# Vanocni.net
KiCad netlist of a schematic drawn in EAGLE
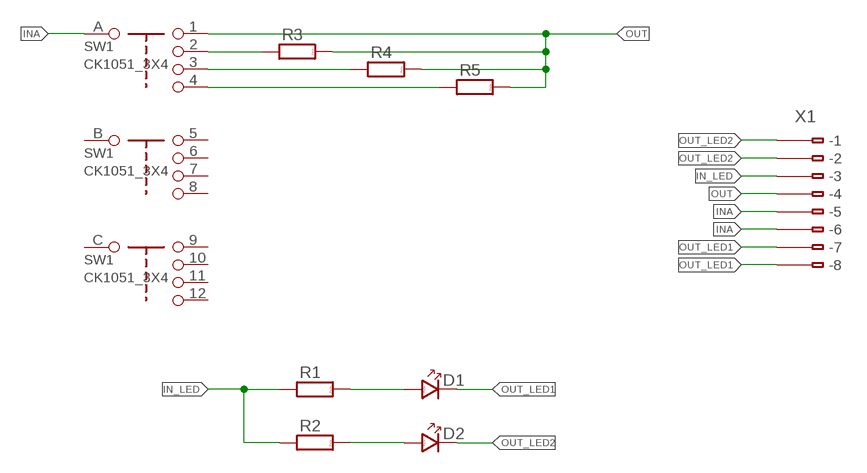
[diagram p0: schematic, sheet 1]

(export (version "E")
  (design (tool "Eeschema 10.0.6"))
  (components
    (comp (ref "D1")
      (value "LED_5")
      (footprint "eagle-import:LED_5")
      (libsource (lib "eagle-import") (part "LED_5"))
    )
    (comp (ref "D2")
      (value "LED_5")
      (footprint "eagle-import:LED_5")
      (libsource (lib "eagle-import") (part "LED_5"))
    )
    (comp (ref "R1")
      (value "R_7,5")
      (footprint "eagle-import:R-7,5")
      (libsource (lib "eagle-import") (part "R_7,5"))
    )
    (comp (ref "R2")
      (value "R_7,5")
      (footprint "eagle-import:R-7,5")
      (libsource (lib "eagle-import") (part "R_7,5"))
    )
    (comp (ref "R3")
      (value "R__2W")
      (footprint "eagle-import:R-_2W")
      (libsource (lib "eagle-import") (part "R__2W"))
    )
    (comp (ref "R4")
      (value "R__2W")
      (footprint "eagle-import:R-_2W")
      (libsource (lib "eagle-import") (part "R__2W"))
    )
    (comp (ref "R5")
      (value "R__2W")
      (footprint "eagle-import:R-_2W")
      (libsource (lib "eagle-import") (part "R__2W"))
    )
    (comp (ref "SW1")
      (value "CK1051_3X4")
      (footprint "eagle-import:SWITCH3X4")
      (libsource (lib "eagle-import") (part "CK1051_3X4"))
    )
    (comp (ref "X1")
      (value "233-508")
      (footprint "eagle-import:233-508")
      (fields (field (name "MF") "Wago Corporation") (field (name "MPN") "0233-0508"))
      (libsource (lib "eagle-import") (part "233-508"))
    )
  )
  (nets
    (net (code "1") (name "INA") (class "Default")
      (node (ref "SW1") (pin "A") (pinfunction "A_A") (pintype "passive"))
      (node (ref "X1") (pin "B5") (pinfunction "B-5_B5") (pintype "passive"))
      (node (ref "X1") (pin "B6") (pinfunction "B-6_B6") (pintype "passive"))
    )
    (net (code "2") (name "IN_LED") (class "Default")
      (node (ref "R1") (pin "1") (pinfunction "1_1") (pintype "passive"))
      (node (ref "R2") (pin "1") (pinfunction "1_1") (pintype "passive"))
      (node (ref "X1") (pin "B3") (pinfunction "B-3_B3") (pintype "passive"))
    )
    (net (code "3") (name "Net-(D1-PadA)") (class "Default")
      (node (ref "D1") (pin "A") (pinfunction "A_A") (pintype "passive"))
      (node (ref "R1") (pin "2") (pinfunction "2_2") (pintype "passive"))
    )
    (net (code "4") (name "Net-(D2-PadA)") (class "Default")
      (node (ref "D2") (pin "A") (pinfunction "A_A") (pintype "passive"))
      (node (ref "R2") (pin "2") (pinfunction "2_2") (pintype "passive"))
    )
    (net (code "5") (name "Net-(R3-Pad1)") (class "Default")
      (node (ref "R3") (pin "1") (pinfunction "1_1") (pintype "passive"))
      (node (ref "SW1") (pin "2") (pinfunction "2_2") (pintype "passive"))
    )
    (net (code "6") (name "Net-(R4-Pad1)") (class "Default")
      (node (ref "R4") (pin "1") (pinfunction "1_1") (pintype "passive"))
      (node (ref "SW1") (pin "3") (pinfunction "3_3") (pintype "passive"))
    )
    (net (code "7") (name "Net-(R5-Pad1)") (class "Default")
      (node (ref "R5") (pin "1") (pinfunction "1_1") (pintype "passive"))
      (node (ref "SW1") (pin "4") (pinfunction "4_4") (pintype "passive"))
    )
    (net (code "8") (name "OUT") (class "Default")
      (node (ref "R3") (pin "2") (pinfunction "2_2") (pintype "passive"))
      (node (ref "R4") (pin "2") (pinfunction "2_2") (pintype "passive"))
      (node (ref "R5") (pin "2") (pinfunction "2_2") (pintype "passive"))
      (node (ref "SW1") (pin "1") (pinfunction "1_1") (pintype "passive"))
      (node (ref "X1") (pin "B4") (pinfunction "B-4_B4") (pintype "passive"))
    )
    (net (code "9") (name "OUT_LED1") (class "Default")
      (node (ref "D1") (pin "K") (pinfunction "K_K") (pintype "passive"))
      (node (ref "X1") (pin "B7") (pinfunction "B-7_B7") (pintype "passive"))
      (node (ref "X1") (pin "B8") (pinfunction "B-8_B8") (pintype "passive"))
    )
    (net (code "10") (name "OUT_LED2") (class "Default")
      (node (ref "D2") (pin "K") (pinfunction "K_K") (pintype "passive"))
      (node (ref "X1") (pin "B1") (pinfunction "B-1_B1") (pintype "passive"))
      (node (ref "X1") (pin "B2") (pinfunction "B-2_B2") (pintype "passive"))
    )
    (net (code "11") (name "unconnected-(SW1B-1-Pad5)") (class "Default")
      (node (ref "SW1") (pin "5") (pinfunction "1_5") (pintype "passive"))
    )
    (net (code "12") (name "unconnected-(SW1B-2-Pad6)") (class "Default")
      (node (ref "SW1") (pin "6") (pinfunction "2_6") (pintype "passive"))
    )
    (net (code "13") (name "unconnected-(SW1B-3-Pad7)") (class "Default")
      (node (ref "SW1") (pin "7") (pinfunction "3_7") (pintype "passive"))
    )
    (net (code "14") (name "unconnected-(SW1B-4-Pad8)") (class "Default")
      (node (ref "SW1") (pin "8") (pinfunction "4_8") (pintype "passive"))
    )
    (net (code "15") (name "unconnected-(SW1B-A-PadB)") (class "Default")
      (node (ref "SW1") (pin "B") (pinfunction "A_B") (pintype "passive"))
    )
    (net (code "16") (name "unconnected-(SW1C-1-Pad9)") (class "Default")
      (node (ref "SW1") (pin "9") (pinfunction "1_9") (pintype "passive"))
    )
    (net (code "17") (name "unconnected-(SW1C-2-Pad10)") (class "Default")
      (node (ref "SW1") (pin "10") (pinfunction "2_10") (pintype "passive"))
    )
    (net (code "18") (name "unconnected-(SW1C-3-Pad11)") (class "Default")
      (node (ref "SW1") (pin "11") (pinfunction "3_11") (pintype "passive"))
    )
    (net (code "19") (name "unconnected-(SW1C-4-Pad12)") (class "Default")
      (node (ref "SW1") (pin "12") (pinfunction "4_12") (pintype "passive"))
    )
    (net (code "20") (name "unconnected-(SW1C-A-PadC)") (class "Default")
      (node (ref "SW1") (pin "C") (pinfunction "A_C") (pintype "passive"))
    )
    (net (code "21") (name "unconnected-(X1--1-PadA1)") (class "Default")
      (node (ref "X1") (pin "A1") (pinfunction "-1_A1") (pintype "passive"))
    )
    (net (code "22") (name "unconnected-(X1--2-PadA2)") (class "Default")
      (node (ref "X1") (pin "A2") (pinfunction "-2_A2") (pintype "passive"))
    )
    (net (code "23") (name "unconnected-(X1--3-PadA3)") (class "Default")
      (node (ref "X1") (pin "A3") (pinfunction "-3_A3") (pintype "passive"))
    )
    (net (code "24") (name "unconnected-(X1--4-PadA4)") (class "Default")
      (node (ref "X1") (pin "A4") (pinfunction "-4_A4") (pintype "passive"))
    )
    (net (code "25") (name "unconnected-(X1--5-PadA5)") (class "Default")
      (node (ref "X1") (pin "A5") (pinfunction "-5_A5") (pintype "passive"))
    )
    (net (code "26") (name "unconnected-(X1--6-PadA6)") (class "Default")
      (node (ref "X1") (pin "A6") (pinfunction "-6_A6") (pintype "passive"))
    )
    (net (code "27") (name "unconnected-(X1--7-PadA7)") (class "Default")
      (node (ref "X1") (pin "A7") (pinfunction "-7_A7") (pintype "passive"))
    )
    (net (code "28") (name "unconnected-(X1--8-PadA8)") (class "Default")
      (node (ref "X1") (pin "A8") (pinfunction "-8_A8") (pintype "passive"))
    )
  )
)
